# RF_Board.net
KiCad netlist of a schematic drawn in EAGLE
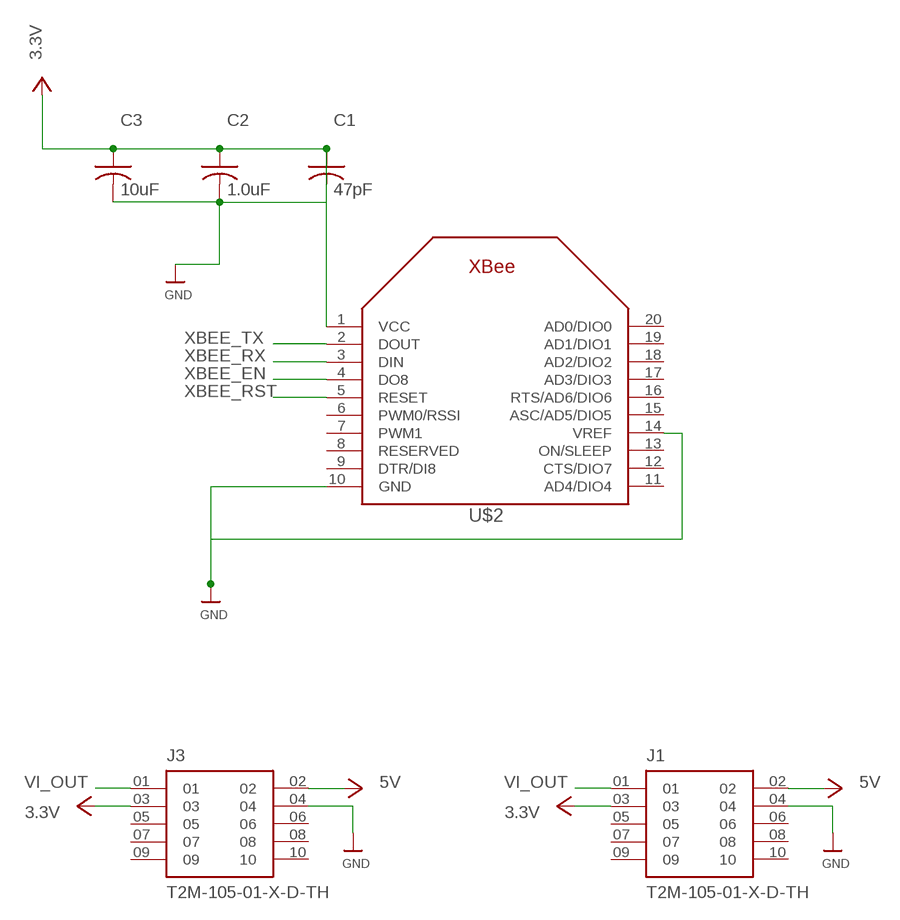
[diagram p0: schematic, sheet 1]

(export (version "E")
  (design (tool "Eeschema 10.0.6"))
  (components
    (comp (ref "C1")
      (value "47pF")
      (footprint "eagle-import:C025-024X044")
      (libsource (lib "eagle-import") (part "C-US025-024X044"))
    )
    (comp (ref "C2")
      (value "1.0uF")
      (footprint "eagle-import:C025-024X044")
      (libsource (lib "eagle-import") (part "C-US025-024X044"))
    )
    (comp (ref "C3")
      (value "10uF")
      (footprint "eagle-import:C025-024X044")
      (libsource (lib "eagle-import") (part "C-US025-024X044"))
    )
    (comp (ref "J1")
      (value "T2M-105-01-X-D-TH")
      (footprint "eagle-import:SAMTEC_T2M-105-01-X-D-TH")
      (fields (field (name "MANUFACTURER") "Samtec"))
      (libsource (lib "eagle-import") (part "T2M-105-01-X-D-TH"))
    )
    (comp (ref "J3")
      (value "T2M-105-01-X-D-TH")
      (footprint "eagle-import:SAMTEC_T2M-105-01-X-D-TH")
      (fields (field (name "MANUFACTURER") "Samtec"))
      (libsource (lib "eagle-import") (part "T2M-105-01-X-D-TH"))
    )
    (comp (ref "U$2")
      (value "XBEE")
      (footprint "eagle-import:XBEE")
      (libsource (lib "eagle-import") (part "XBEE"))
    )
  )
  (nets
    (net (code "1") (name "/VI_OUT") (class "Default")
      (node (ref "J1") (pin "01") (pinfunction "01_01") (pintype "passive"))
      (node (ref "J3") (pin "01") (pinfunction "01_01") (pintype "passive"))
    )
    (net (code "2") (name "/XBEE_EN") (class "Default")
      (node (ref "U$2") (pin "4") (pinfunction "DO8_4") (pintype "output"))
    )
    (net (code "3") (name "/XBEE_RST") (class "Default")
      (node (ref "U$2") (pin "5") (pinfunction "RESET_5") (pintype "input"))
    )
    (net (code "4") (name "/XBEE_RX") (class "Default")
      (node (ref "U$2") (pin "3") (pinfunction "DIN_3") (pintype "input"))
    )
    (net (code "5") (name "/XBEE_TX") (class "Default")
      (node (ref "U$2") (pin "2") (pinfunction "DOUT_2") (pintype "output"))
    )
    (net (code "6") (name "3.3V") (class "Default")
      (node (ref "C1") (pin "1") (pinfunction "1_1") (pintype "passive"))
      (node (ref "C2") (pin "1") (pinfunction "1_1") (pintype "passive"))
      (node (ref "C3") (pin "1") (pinfunction "1_1") (pintype "passive"))
      (node (ref "J1") (pin "02") (pinfunction "02_02") (pintype "passive"))
      (node (ref "J1") (pin "03") (pinfunction "03_03") (pintype "passive"))
      (node (ref "J3") (pin "02") (pinfunction "02_02") (pintype "passive"))
      (node (ref "J3") (pin "03") (pinfunction "03_03") (pintype "passive"))
      (node (ref "U$2") (pin "1") (pinfunction "VCC_1") (pintype "power_in"))
    )
    (net (code "7") (name "GND") (class "Default")
      (node (ref "C1") (pin "2") (pinfunction "2_2") (pintype "passive"))
      (node (ref "C2") (pin "2") (pinfunction "2_2") (pintype "passive"))
      (node (ref "C3") (pin "2") (pinfunction "2_2") (pintype "passive"))
      (node (ref "J1") (pin "04") (pinfunction "04_04") (pintype "passive"))
      (node (ref "J3") (pin "04") (pinfunction "04_04") (pintype "passive"))
      (node (ref "U$2") (pin "10") (pinfunction "GND_10") (pintype "power_in"))
      (node (ref "U$2") (pin "14") (pinfunction "VREF_14") (pintype "input"))
    )
    (net (code "8") (name "unconnected-(J1-Pad05)") (class "Default")
      (node (ref "J1") (pin "05") (pinfunction "05_05") (pintype "passive"))
    )
    (net (code "9") (name "unconnected-(J1-Pad06)") (class "Default")
      (node (ref "J1") (pin "06") (pinfunction "06_06") (pintype "passive"))
    )
    (net (code "10") (name "unconnected-(J1-Pad07)") (class "Default")
      (node (ref "J1") (pin "07") (pinfunction "07_07") (pintype "passive"))
    )
    (net (code "11") (name "unconnected-(J1-Pad08)") (class "Default")
      (node (ref "J1") (pin "08") (pinfunction "08_08") (pintype "passive"))
    )
    (net (code "12") (name "unconnected-(J1-Pad09)") (class "Default")
      (node (ref "J1") (pin "09") (pinfunction "09_09") (pintype "passive"))
    )
    (net (code "13") (name "unconnected-(J1-Pad10)") (class "Default")
      (node (ref "J1") (pin "10") (pinfunction "10_10") (pintype "passive"))
    )
    (net (code "14") (name "unconnected-(J3-Pad05)") (class "Default")
      (node (ref "J3") (pin "05") (pinfunction "05_05") (pintype "passive"))
    )
    (net (code "15") (name "unconnected-(J3-Pad06)") (class "Default")
      (node (ref "J3") (pin "06") (pinfunction "06_06") (pintype "passive"))
    )
    (net (code "16") (name "unconnected-(J3-Pad07)") (class "Default")
      (node (ref "J3") (pin "07") (pinfunction "07_07") (pintype "passive"))
    )
    (net (code "17") (name "unconnected-(J3-Pad08)") (class "Default")
      (node (ref "J3") (pin "08") (pinfunction "08_08") (pintype "passive"))
    )
    (net (code "18") (name "unconnected-(J3-Pad09)") (class "Default")
      (node (ref "J3") (pin "09") (pinfunction "09_09") (pintype "passive"))
    )
    (net (code "19") (name "unconnected-(J3-Pad10)") (class "Default")
      (node (ref "J3") (pin "10") (pinfunction "10_10") (pintype "passive"))
    )
    (net (code "20") (name "unconnected-(U$2-AD0{slash}DIO0-Pad20)") (class "Default")
      (node (ref "U$2") (pin "20") (pinfunction "AD0/DIO0_20") (pintype "bidirectional"))
    )
    (net (code "21") (name "unconnected-(U$2-AD1{slash}DIO1-Pad19)") (class "Default")
      (node (ref "U$2") (pin "19") (pinfunction "AD1/DIO1_19") (pintype "bidirectional"))
    )
    (net (code "22") (name "unconnected-(U$2-AD2{slash}DIO2-Pad18)") (class "Default")
      (node (ref "U$2") (pin "18") (pinfunction "AD2/DIO2_18") (pintype "bidirectional"))
    )
    (net (code "23") (name "unconnected-(U$2-AD3{slash}DIO3-Pad17)") (class "Default")
      (node (ref "U$2") (pin "17") (pinfunction "AD3/DIO3_17") (pintype "bidirectional"))
    )
    (net (code "24") (name "unconnected-(U$2-AD4{slash}DIO4-Pad11)") (class "Default")
      (node (ref "U$2") (pin "11") (pinfunction "AD4/DIO4_11") (pintype "bidirectional"))
    )
    (net (code "25") (name "unconnected-(U$2-ASC{slash}AD5{slash}DIO5-Pad15)") (class "Default")
      (node (ref "U$2") (pin "15") (pinfunction "ASC/AD5/DIO5_15") (pintype "bidirectional"))
    )
    (net (code "26") (name "unconnected-(U$2-CTS{slash}DIO7-Pad12)") (class "Default")
      (node (ref "U$2") (pin "12") (pinfunction "CTS/DIO7_12") (pintype "bidirectional"))
    )
    (net (code "27") (name "unconnected-(U$2-DTR{slash}DI8-Pad9)") (class "Default")
      (node (ref "U$2") (pin "9") (pinfunction "DTR/DI8_9") (pintype "input"))
    )
    (net (code "28") (name "unconnected-(U$2-ON{slash}SLEEP-Pad13)") (class "Default")
      (node (ref "U$2") (pin "13") (pinfunction "ON/SLEEP_13") (pintype "output"))
    )
    (net (code "29") (name "unconnected-(U$2-PWM0{slash}RSSI-Pad6)") (class "Default")
      (node (ref "U$2") (pin "6") (pinfunction "PWM0/RSSI_6") (pintype "output"))
    )
    (net (code "30") (name "unconnected-(U$2-PWM1-Pad7)") (class "Default")
      (node (ref "U$2") (pin "7") (pinfunction "PWM1_7") (pintype "output"))
    )
    (net (code "31") (name "unconnected-(U$2-RESERVED-Pad8)") (class "Default")
      (node (ref "U$2") (pin "8") (pinfunction "RESERVED_8") (pintype "no_connect"))
    )
    (net (code "32") (name "unconnected-(U$2-RTS{slash}AD6{slash}DIO6-Pad16)") (class "Default")
      (node (ref "U$2") (pin "16") (pinfunction "RTS/AD6/DIO6_16") (pintype "bidirectional"))
    )
  )
)
